# SparkFun_Ardumoto.net
KiCad netlist of a schematic drawn in EAGLE
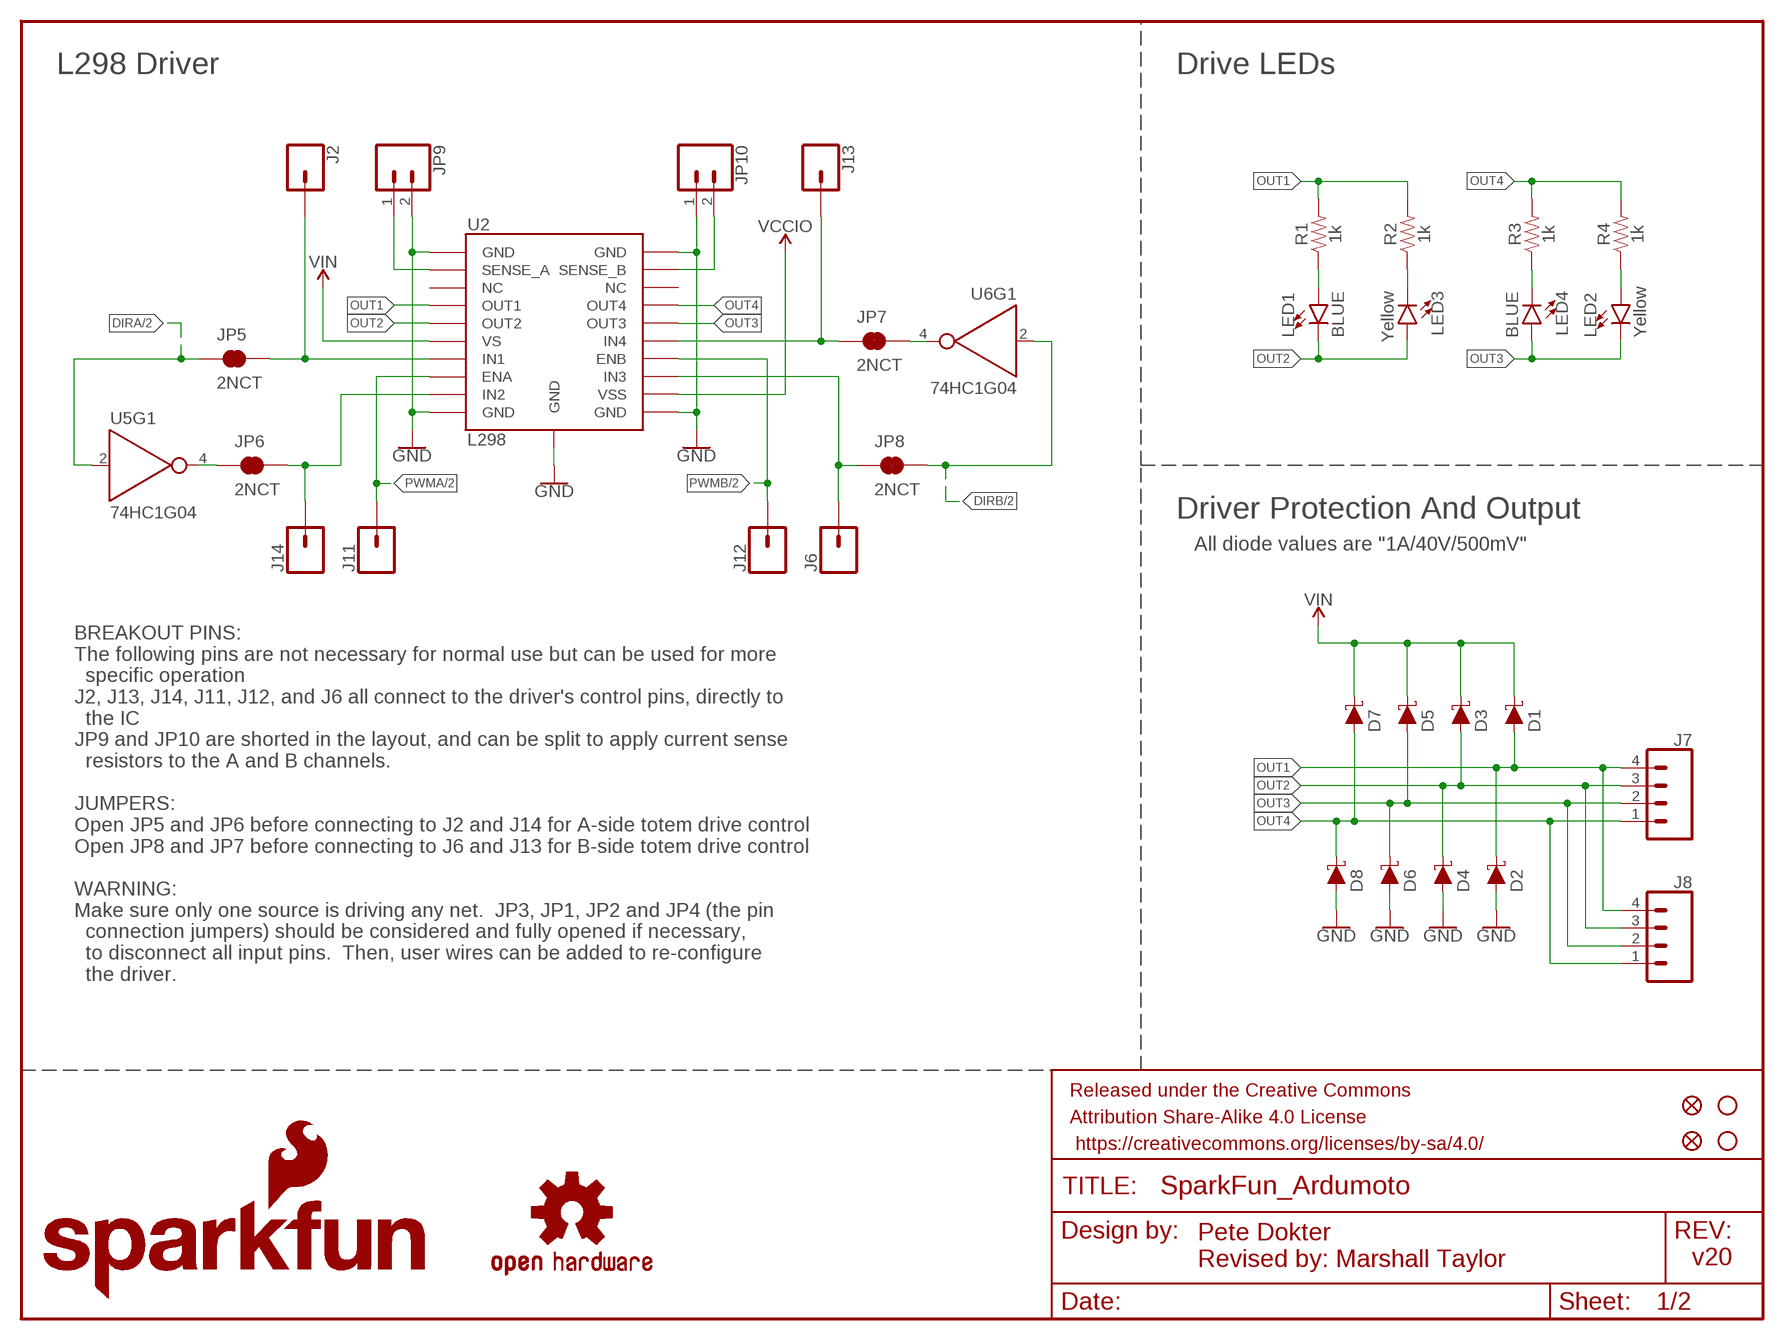
[diagram p0: schematic, sheet 1]
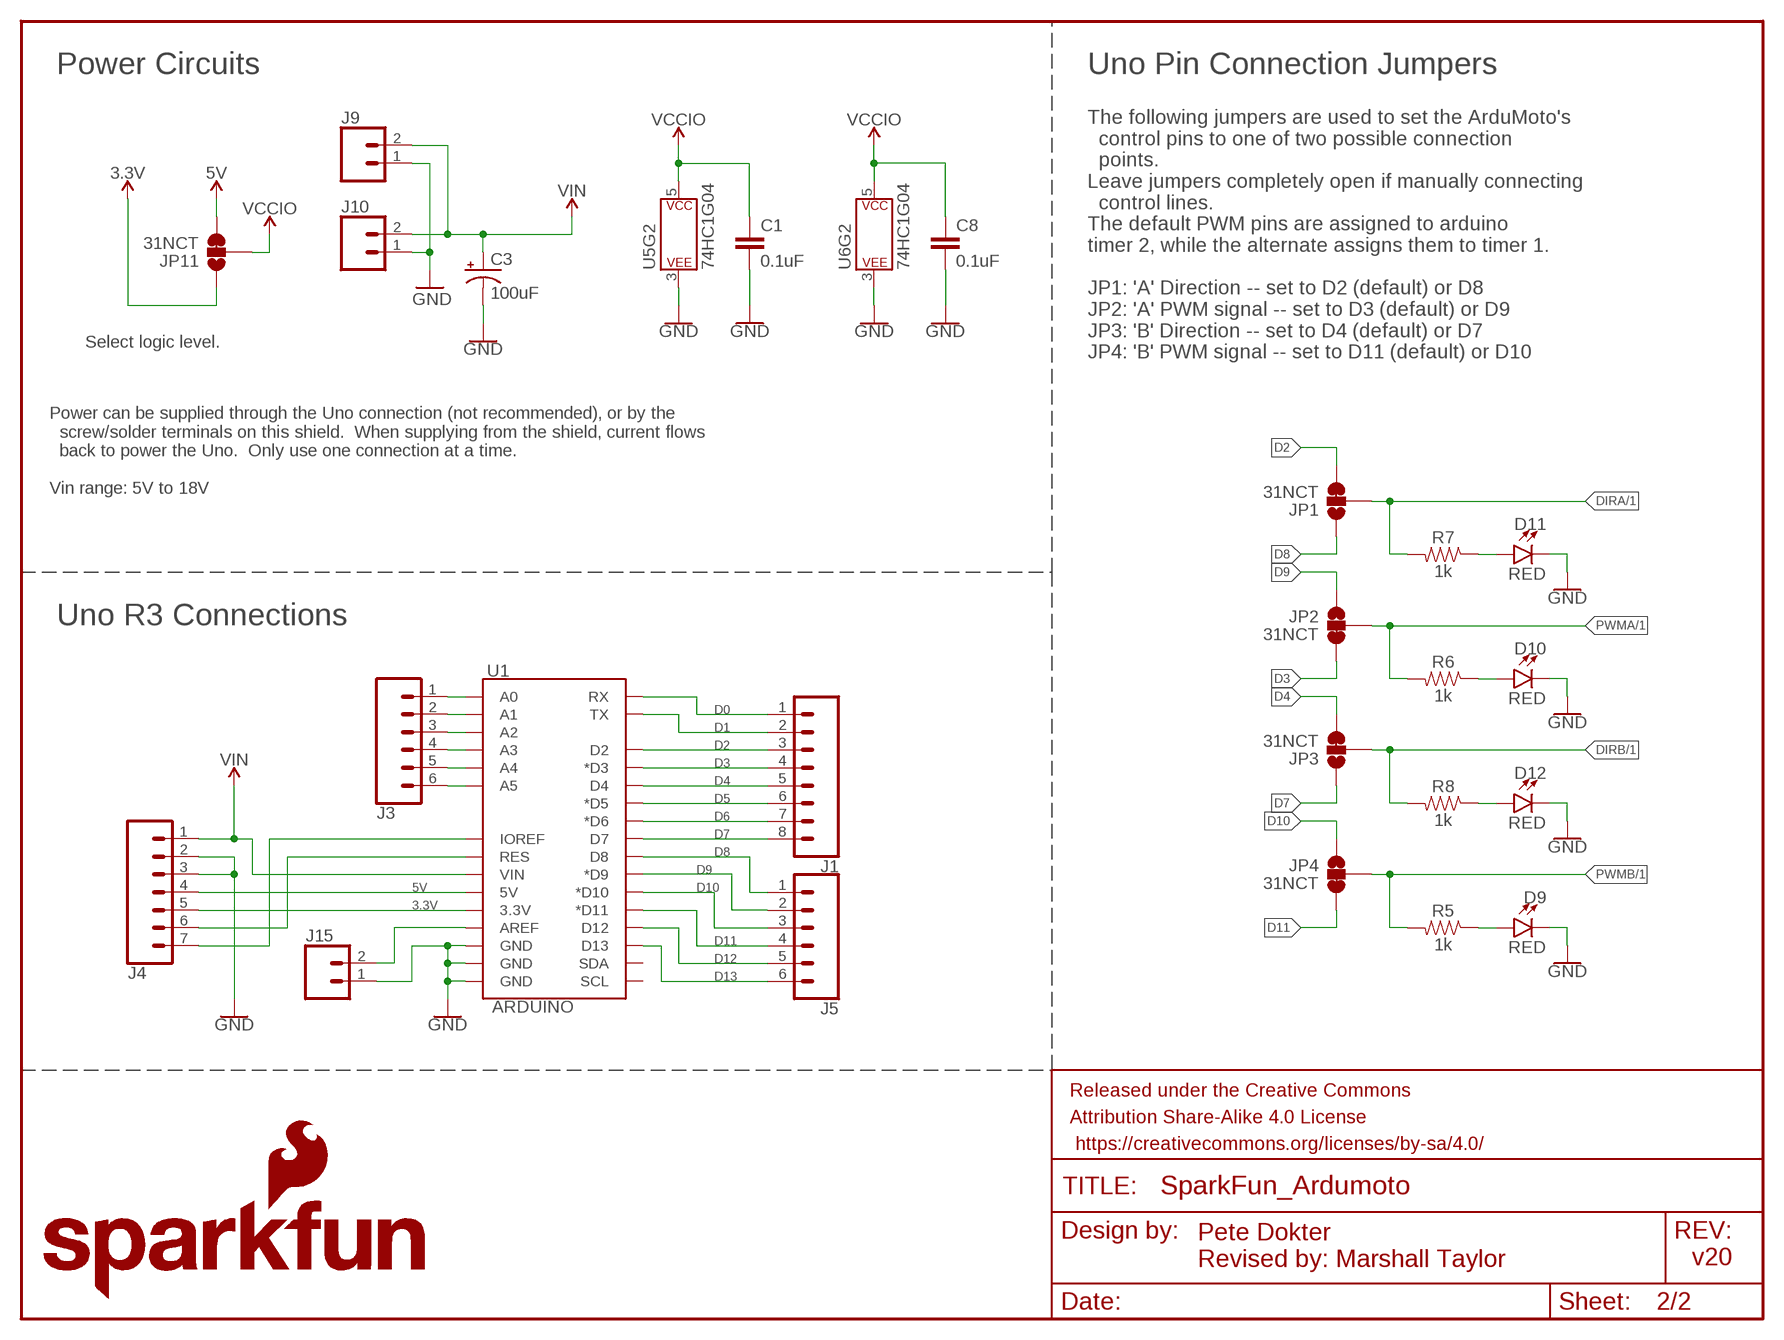
[diagram p1: schematic, sheet 2]

(export (version "E")
  (design (tool "Eeschema 10.0.6"))
  (components
    (comp (ref "D1")
      (value "1A/40V/500mV")
      (footprint "eagle-import:SMA-DIODE")
      (libsource (lib "eagle-import") (part "DIODE-SCHOTTKY-SS14"))
    )
    (comp (ref "D2")
      (value "1A/40V/500mV")
      (footprint "eagle-import:SMA-DIODE")
      (libsource (lib "eagle-import") (part "DIODE-SCHOTTKY-SS14"))
    )
    (comp (ref "D3")
      (value "1A/40V/500mV")
      (footprint "eagle-import:SMA-DIODE")
      (libsource (lib "eagle-import") (part "DIODE-SCHOTTKY-SS14"))
    )
    (comp (ref "D4")
      (value "1A/40V/500mV")
      (footprint "eagle-import:SMA-DIODE")
      (libsource (lib "eagle-import") (part "DIODE-SCHOTTKY-SS14"))
    )
    (comp (ref "D5")
      (value "1A/40V/500mV")
      (footprint "eagle-import:SMA-DIODE")
      (libsource (lib "eagle-import") (part "DIODE-SCHOTTKY-SS14"))
    )
    (comp (ref "D6")
      (value "1A/40V/500mV")
      (footprint "eagle-import:SMA-DIODE")
      (libsource (lib "eagle-import") (part "DIODE-SCHOTTKY-SS14"))
    )
    (comp (ref "D7")
      (value "1A/40V/500mV")
      (footprint "eagle-import:SMA-DIODE")
      (libsource (lib "eagle-import") (part "DIODE-SCHOTTKY-SS14"))
    )
    (comp (ref "D8")
      (value "1A/40V/500mV")
      (footprint "eagle-import:SMA-DIODE")
      (libsource (lib "eagle-import") (part "DIODE-SCHOTTKY-SS14"))
    )
    (comp (ref "FD1")
      (value "FIDUCIALUFIDUCIAL")
      (footprint "eagle-import:MICRO-FIDUCIAL")
      (libsource (lib "eagle-import") (part "FIDUCIALUFIDUCIAL"))
    )
    (comp (ref "FD2")
      (value "FIDUCIALUFIDUCIAL")
      (footprint "eagle-import:MICRO-FIDUCIAL")
      (libsource (lib "eagle-import") (part "FIDUCIALUFIDUCIAL"))
    )
    (comp (ref "FRAME2")
      (value "FRAME-LETTERNO_PACKAGE")
      (footprint "eagle-import:DUMMY")
      (fields (field (name "DESIGNER") "Nobody"))
      (libsource (lib "eagle-import") (part "FRAME-LETTERNO_PACKAGE"))
    )
    (comp (ref "H1")
      (value "STAND-OFF")
      (footprint "eagle-import:STAND-OFF")
      (libsource (lib "eagle-import") (part "STAND-OFF"))
    )
    (comp (ref "H2")
      (value "STAND-OFF")
      (footprint "eagle-import:STAND-OFF")
      (libsource (lib "eagle-import") (part "STAND-OFF"))
    )
    (comp (ref "J2")
      (value "CONN_01PTH_NO_SILK_YES_STOP")
      (footprint "eagle-import:1X01_NO_SILK")
      (libsource (lib "eagle-import") (part "CONN_01PTH_NO_SILK_YES_STOP"))
    )
    (comp (ref "J6")
      (value "CONN_01PTH_NO_SILK_YES_STOP")
      (footprint "eagle-import:1X01_NO_SILK")
      (libsource (lib "eagle-import") (part "CONN_01PTH_NO_SILK_YES_STOP"))
    )
    (comp (ref "J7")
      (value "CONN_04SCREW")
      (footprint "eagle-import:SCREWTERMINAL-3.5MM-4")
      (libsource (lib "eagle-import") (part "CONN_04SCREW"))
    )
    (comp (ref "J8")
      (value "CONN_04")
      (footprint "eagle-import:1X04")
      (libsource (lib "eagle-import") (part "CONN_04"))
    )
    (comp (ref "J11")
      (value "CONN_01PTH_NO_SILK_YES_STOP")
      (footprint "eagle-import:1X01_NO_SILK")
      (libsource (lib "eagle-import") (part "CONN_01PTH_NO_SILK_YES_STOP"))
    )
    (comp (ref "J12")
      (value "CONN_01PTH_NO_SILK_YES_STOP")
      (footprint "eagle-import:1X01_NO_SILK")
      (libsource (lib "eagle-import") (part "CONN_01PTH_NO_SILK_YES_STOP"))
    )
    (comp (ref "J13")
      (value "CONN_01PTH_NO_SILK_YES_STOP")
      (footprint "eagle-import:1X01_NO_SILK")
      (libsource (lib "eagle-import") (part "CONN_01PTH_NO_SILK_YES_STOP"))
    )
    (comp (ref "J14")
      (value "CONN_01PTH_NO_SILK_YES_STOP")
      (footprint "eagle-import:1X01_NO_SILK")
      (libsource (lib "eagle-import") (part "CONN_01PTH_NO_SILK_YES_STOP"))
    )
    (comp (ref "JP5")
      (value "2NCT")
      (footprint "eagle-import:SMT-JUMPER_2_NC_TRACE_SILK")
      (libsource (lib "eagle-import") (part "JUMPER-SMT_2_NC_TRACE_SILK"))
    )
    (comp (ref "JP6")
      (value "2NCT")
      (footprint "eagle-import:SMT-JUMPER_2_NC_TRACE_SILK")
      (libsource (lib "eagle-import") (part "JUMPER-SMT_2_NC_TRACE_SILK"))
    )
    (comp (ref "JP7")
      (value "2NCT")
      (footprint "eagle-import:SMT-JUMPER_2_NC_TRACE_SILK")
      (libsource (lib "eagle-import") (part "JUMPER-SMT_2_NC_TRACE_SILK"))
    )
    (comp (ref "JP8")
      (value "2NCT")
      (footprint "eagle-import:SMT-JUMPER_2_NC_TRACE_SILK")
      (libsource (lib "eagle-import") (part "JUMPER-SMT_2_NC_TRACE_SILK"))
    )
    (comp (ref "JP9")
      (value "CONN_021X02_NO_SILK")
      (footprint "eagle-import:1X02_NO_SILK")
      (libsource (lib "eagle-import") (part "CONN_021X02_NO_SILK"))
    )
    (comp (ref "JP10")
      (value "CONN_021X02_NO_SILK")
      (footprint "eagle-import:1X02_NO_SILK")
      (libsource (lib "eagle-import") (part "CONN_021X02_NO_SILK"))
    )
    (comp (ref "LED1")
      (value "BLUE")
      (footprint "eagle-import:LED-0603")
      (libsource (lib "eagle-import") (part "LED-BLUE0603"))
    )
    (comp (ref "LED2")
      (value "Yellow")
      (footprint "eagle-import:LED-0603")
      (libsource (lib "eagle-import") (part "LED-YELLOW0603"))
    )
    (comp (ref "LED3")
      (value "Yellow")
      (footprint "eagle-import:LED-0603")
      (libsource (lib "eagle-import") (part "LED-YELLOW0603"))
    )
    (comp (ref "LED4")
      (value "BLUE")
      (footprint "eagle-import:LED-0603")
      (libsource (lib "eagle-import") (part "LED-BLUE0603"))
    )
    (comp (ref "LOGO2")
      (value "SFE_LOGO_NAME_FLAME.1_INCH")
      (footprint "eagle-import:SFE_LOGO_NAME_FLAME_.1")
      (libsource (lib "eagle-import") (part "SFE_LOGO_NAME_FLAME.1_INCH"))
    )
    (comp (ref "R1")
      (value "1k")
      (footprint "eagle-import:0603")
      (libsource (lib "eagle-import") (part "1KOHM-0603-1/10W-1%"))
    )
    (comp (ref "R2")
      (value "1k")
      (footprint "eagle-import:0603")
      (libsource (lib "eagle-import") (part "1KOHM-0603-1/10W-1%"))
    )
    (comp (ref "R3")
      (value "1k")
      (footprint "eagle-import:0603")
      (libsource (lib "eagle-import") (part "1KOHM-0603-1/10W-1%"))
    )
    (comp (ref "R4")
      (value "1k")
      (footprint "eagle-import:0603")
      (libsource (lib "eagle-import") (part "1KOHM-0603-1/10W-1%"))
    )
    (comp (ref "U$1")
      (value "OSHW-LOGOS")
      (footprint "eagle-import:OSHW-LOGO-S")
      (libsource (lib "eagle-import") (part "OSHW-LOGOS"))
    )
    (comp (ref "U2")
      (value "L298")
      (footprint "eagle-import:POWERSO20_L298_PAD")
      (libsource (lib "eagle-import") (part "L298_SMD_W_PAD"))
    )
    (comp (ref "U5")
      (value "74HC1G04")
      (footprint "eagle-import:SOT353")
      (libsource (lib "eagle-import") (part "741G04HC"))
    )
    (comp (ref "U6")
      (value "74HC1G04")
      (footprint "eagle-import:SOT353")
      (libsource (lib "eagle-import") (part "741G04HC"))
    )
    (comp (ref "C1")
      (value "0.1uF")
      (footprint "eagle-import:0603")
      (libsource (lib "eagle-import") (part "0.1UF-0603-25V-5%"))
    )
    (comp (ref "C3")
      (value "100uF")
      (footprint "eagle-import:PANASONIC_D")
      (libsource (lib "eagle-import") (part "100UF-POLAR-25V-20%(ELEC)"))
    )
    (comp (ref "C8")
      (value "0.1uF")
      (footprint "eagle-import:0603")
      (libsource (lib "eagle-import") (part "0.1UF-0603-25V-5%"))
    )
    (comp (ref "D9")
      (value "RED")
      (footprint "eagle-import:LED-0603")
      (libsource (lib "eagle-import") (part "LED-RED0603"))
    )
    (comp (ref "D10")
      (value "RED")
      (footprint "eagle-import:LED-0603")
      (libsource (lib "eagle-import") (part "LED-RED0603"))
    )
    (comp (ref "D11")
      (value "RED")
      (footprint "eagle-import:LED-0603")
      (libsource (lib "eagle-import") (part "LED-RED0603"))
    )
    (comp (ref "D12")
      (value "RED")
      (footprint "eagle-import:LED-0603")
      (libsource (lib "eagle-import") (part "LED-RED0603"))
    )
    (comp (ref "FRAME1")
      (value "FRAME-LETTER")
      (footprint "eagle-import:CREATIVE_COMMONS")
      (libsource (lib "eagle-import") (part "FRAME-LETTER"))
    )
    (comp (ref "J1")
      (value "CONN_08NO_SILK_FEMALE_PTH")
      (footprint "eagle-import:1X08_NO_SILK")
      (libsource (lib "eagle-import") (part "CONN_08NO_SILK_FEMALE_PTH"))
    )
    (comp (ref "J3")
      (value "CONN_06NO_SILK_FEMALE_PTH")
      (footprint "eagle-import:1X06_NO_SILK")
      (libsource (lib "eagle-import") (part "CONN_06NO_SILK_FEMALE_PTH"))
    )
    (comp (ref "J4")
      (value "CONN_07NO_SILK")
      (footprint "eagle-import:1X07_NO_SILK")
      (libsource (lib "eagle-import") (part "CONN_07NO_SILK"))
    )
    (comp (ref "J5")
      (value "CONN_06NO_SILK_FEMALE_PTH")
      (footprint "eagle-import:1X06_NO_SILK")
      (libsource (lib "eagle-import") (part "CONN_06NO_SILK_FEMALE_PTH"))
    )
    (comp (ref "J9")
      (value "CONN_02")
      (footprint "eagle-import:1X02")
      (libsource (lib "eagle-import") (part "CONN_02"))
    )
    (comp (ref "J10")
      (value "CONN_023.5MM")
      (footprint "eagle-import:SCREWTERMINAL-3.5MM-2")
      (libsource (lib "eagle-import") (part "CONN_023.5MM"))
    )
    (comp (ref "J15")
      (value "CONN_021X02_NO_SILK")
      (footprint "eagle-import:1X02_NO_SILK")
      (libsource (lib "eagle-import") (part "CONN_021X02_NO_SILK"))
    )
    (comp (ref "JP1")
      (value "31NCT")
      (footprint "eagle-import:SMT-JUMPER_3_1-NC_TRACE_SILK")
      (libsource (lib "eagle-import") (part "JUMPER-SMT_3_1-NC_TRACE_SILK"))
    )
    (comp (ref "JP2")
      (value "31NCT")
      (footprint "eagle-import:SMT-JUMPER_3_1-NC_TRACE_SILK")
      (libsource (lib "eagle-import") (part "JUMPER-SMT_3_1-NC_TRACE_SILK"))
    )
    (comp (ref "JP3")
      (value "31NCT")
      (footprint "eagle-import:SMT-JUMPER_3_1-NC_TRACE_SILK")
      (libsource (lib "eagle-import") (part "JUMPER-SMT_3_1-NC_TRACE_SILK"))
    )
    (comp (ref "JP4")
      (value "31NCT")
      (footprint "eagle-import:SMT-JUMPER_3_1-NC_TRACE_SILK")
      (libsource (lib "eagle-import") (part "JUMPER-SMT_3_1-NC_TRACE_SILK"))
    )
    (comp (ref "JP11")
      (value "31NCT")
      (footprint "eagle-import:SMT-JUMPER_3_1-NC_TRACE_SILK")
      (libsource (lib "eagle-import") (part "JUMPER-SMT_3_1-NC_TRACE_SILK"))
    )
    (comp (ref "LOGO1")
      (value "SFE_LOGO_NAME_FLAME.2_INCH")
      (footprint "eagle-import:SFE_LOGO_NAME_FLAME_.2")
      (libsource (lib "eagle-import") (part "SFE_LOGO_NAME_FLAME.2_INCH"))
    )
    (comp (ref "R5")
      (value "1k")
      (footprint "eagle-import:0603")
      (libsource (lib "eagle-import") (part "1KOHM-0603-1/10W-1%"))
    )
    (comp (ref "R6")
      (value "1k")
      (footprint "eagle-import:0603")
      (libsource (lib "eagle-import") (part "1KOHM-0603-1/10W-1%"))
    )
    (comp (ref "R7")
      (value "1k")
      (footprint "eagle-import:0603")
      (libsource (lib "eagle-import") (part "1KOHM-0603-1/10W-1%"))
    )
    (comp (ref "R8")
      (value "1k")
      (footprint "eagle-import:0603")
      (libsource (lib "eagle-import") (part "1KOHM-0603-1/10W-1%"))
    )
    (comp (ref "U1")
      (value "ARDUINO")
      (footprint "eagle-import:UNO_R3_SHIELD_NOLABELS")
      (libsource (lib "eagle-import") (part "ARDUINO_UNO_R3_SHIELDNOLABELS"))
    )
  )
  (nets
    (net (code "1") (name "3.3V") (class "Default")
      (node (ref "J4") (pin "5") (pinfunction "5_5") (pintype "passive"))
      (node (ref "JP11") (pin "1") (pinfunction "1_1") (pintype "passive"))
      (node (ref "U1") (pin "3.3V") (pinfunction "3.3V_3.3V") (pintype "bidirectional"))
    )
    (net (code "2") (name "5V") (class "Default")
      (node (ref "J4") (pin "4") (pinfunction "4_4") (pintype "passive"))
      (node (ref "JP11") (pin "3") (pinfunction "3_3") (pintype "passive"))
      (node (ref "U1") (pin "5V") (pinfunction "5V_5V") (pintype "bidirectional"))
    )
    (net (code "3") (name "D0") (class "Default")
      (node (ref "J1") (pin "1") (pinfunction "1_1") (pintype "passive"))
      (node (ref "U1") (pin "RX") (pinfunction "RX_RX") (pintype "bidirectional"))
    )
    (net (code "4") (name "D1") (class "Default")
      (node (ref "J1") (pin "2") (pinfunction "2_2") (pintype "passive"))
      (node (ref "U1") (pin "TX") (pinfunction "TX_TX") (pintype "bidirectional"))
    )
    (net (code "5") (name "D2") (class "Default")
      (node (ref "J1") (pin "3") (pinfunction "3_3") (pintype "passive"))
      (node (ref "JP1") (pin "3") (pinfunction "3_3") (pintype "passive"))
      (node (ref "U1") (pin "D2") (pinfunction "D2_D2") (pintype "bidirectional"))
    )
    (net (code "6") (name "D3") (class "Default")
      (node (ref "J1") (pin "4") (pinfunction "4_4") (pintype "passive"))
      (node (ref "JP2") (pin "3") (pinfunction "3_3") (pintype "passive"))
      (node (ref "U1") (pin "D3") (pinfunction "*D3_D3") (pintype "bidirectional"))
    )
    (net (code "7") (name "D4") (class "Default")
      (node (ref "J1") (pin "5") (pinfunction "5_5") (pintype "passive"))
      (node (ref "JP3") (pin "3") (pinfunction "3_3") (pintype "passive"))
      (node (ref "U1") (pin "D4") (pinfunction "D4_D4") (pintype "bidirectional"))
    )
    (net (code "8") (name "D5") (class "Default")
      (node (ref "J1") (pin "6") (pinfunction "6_6") (pintype "passive"))
      (node (ref "U1") (pin "D5") (pinfunction "*D5_D5") (pintype "bidirectional"))
    )
    (net (code "9") (name "D6") (class "Default")
      (node (ref "J1") (pin "7") (pinfunction "7_7") (pintype "passive"))
      (node (ref "U1") (pin "D6") (pinfunction "*D6_D6") (pintype "bidirectional"))
    )
    (net (code "10") (name "D7") (class "Default")
      (node (ref "J1") (pin "8") (pinfunction "8_8") (pintype "passive"))
      (node (ref "JP3") (pin "1") (pinfunction "1_1") (pintype "passive"))
      (node (ref "U1") (pin "D7") (pinfunction "D7_D7") (pintype "bidirectional"))
    )
    (net (code "11") (name "D8") (class "Default")
      (node (ref "J5") (pin "1") (pinfunction "1_1") (pintype "passive"))
      (node (ref "JP1") (pin "1") (pinfunction "1_1") (pintype "passive"))
      (node (ref "U1") (pin "D8") (pinfunction "D8_D8") (pintype "bidirectional"))
    )
    (net (code "12") (name "D9") (class "Default")
      (node (ref "J5") (pin "2") (pinfunction "2_2") (pintype "passive"))
      (node (ref "JP2") (pin "1") (pinfunction "1_1") (pintype "passive"))
      (node (ref "U1") (pin "D9") (pinfunction "*D9_D9") (pintype "bidirectional"))
    )
    (net (code "13") (name "D10") (class "Default")
      (node (ref "J5") (pin "3") (pinfunction "3_3") (pintype "passive"))
      (node (ref "JP4") (pin "1") (pinfunction "1_1") (pintype "passive"))
      (node (ref "U1") (pin "D10") (pinfunction "*D10_D10") (pintype "bidirectional"))
    )
    (net (code "14") (name "D11") (class "Default")
      (node (ref "J5") (pin "4") (pinfunction "4_4") (pintype "passive"))
      (node (ref "JP4") (pin "3") (pinfunction "3_3") (pintype "passive"))
      (node (ref "U1") (pin "D11") (pinfunction "*D11_D11") (pintype "bidirectional"))
    )
    (net (code "15") (name "D12") (class "Default")
      (node (ref "J5") (pin "5") (pinfunction "5_5") (pintype "passive"))
      (node (ref "U1") (pin "D12") (pinfunction "D12_D12") (pintype "bidirectional"))
    )
    (net (code "16") (name "D13") (class "Default")
      (node (ref "J5") (pin "6") (pinfunction "6_6") (pintype "passive"))
      (node (ref "U1") (pin "D13") (pinfunction "D13_D13") (pintype "bidirectional"))
    )
    (net (code "17") (name "DIRA") (class "Default")
      (node (ref "JP1") (pin "2") (pinfunction "2_2") (pintype "passive"))
      (node (ref "JP5") (pin "1") (pinfunction "1_1") (pintype "passive"))
      (node (ref "R7") (pin "2") (pinfunction "2_2") (pintype "passive"))
      (node (ref "U5") (pin "2") (pinfunction "A_2") (pintype "bidirectional"))
    )
    (net (code "18") (name "DIRB") (class "Default")
      (node (ref "JP3") (pin "2") (pinfunction "2_2") (pintype "passive"))
      (node (ref "JP8") (pin "2") (pinfunction "2_2") (pintype "passive"))
      (node (ref "R8") (pin "2") (pinfunction "2_2") (pintype "passive"))
      (node (ref "U6") (pin "2") (pinfunction "A_2") (pintype "bidirectional"))
    )
    (net (code "19") (name "GND") (class "Default")
      (node (ref "C1") (pin "2") (pinfunction "2_2") (pintype "passive"))
      (node (ref "C3") (pin "-") (pinfunction "-_-") (pintype "passive"))
      (node (ref "C8") (pin "2") (pinfunction "2_2") (pintype "passive"))
      (node (ref "D10") (pin "C") (pinfunction "C_C") (pintype "passive"))
      (node (ref "D11") (pin "C") (pinfunction "C_C") (pintype "passive"))
      (node (ref "D12") (pin "C") (pinfunction "C_C") (pintype "passive"))
      (node (ref "D2") (pin "A") (pinfunction "A_A") (pintype "passive"))
      (node (ref "D4") (pin "A") (pinfunction "A_A") (pintype "passive"))
      (node (ref "D6") (pin "A") (pinfunction "A_A") (pintype "passive"))
      (node (ref "D8") (pin "A") (pinfunction "A_A") (pintype "passive"))
      (node (ref "D9") (pin "C") (pinfunction "C_C") (pintype "passive"))
      (node (ref "J10") (pin "1") (pinfunction "1_1") (pintype "passive"))
      (node (ref "J15") (pin "1") (pinfunction "1_1") (pintype "passive"))
      (node (ref "J4") (pin "2") (pinfunction "2_2") (pintype "passive"))
      (node (ref "J4") (pin "3") (pinfunction "3_3") (pintype "passive"))
      (node (ref "J9") (pin "1") (pinfunction "1_1") (pintype "passive"))
      (node (ref "JP10") (pin "1") (pinfunction "1_1") (pintype "passive"))
      (node (ref "JP9") (pin "2") (pinfunction "2_2") (pintype "passive"))
      (node (ref "U1") (pin "GND@0") (pinfunction "GND_GND@0") (pintype "bidirectional"))
      (node (ref "U1") (pin "GND@1") (pinfunction "GND_GND@1") (pintype "bidirectional"))
      (node (ref "U1") (pin "GND@2") (pinfunction "GND_GND@2") (pintype "bidirectional"))
      (node (ref "U2") (pin "1") (pinfunction "GND_1") (pintype "bidirectional"))
      (node (ref "U2") (pin "10") (pinfunction "GND_10") (pintype "bidirectional"))
      (node (ref "U2") (pin "11") (pinfunction "GND_11") (pintype "bidirectional"))
      (node (ref "U2") (pin "20") (pinfunction "GND_20") (pintype "bidirectional"))
      (node (ref "U2") (pin "PAD") (pinfunction "GND_PAD") (pintype "bidirectional"))
      (node (ref "U5") (pin "3") (pinfunction "P$V-_3") (pintype "bidirectional"))
      (node (ref "U6") (pin "3") (pinfunction "P$V-_3") (pintype "bidirectional"))
    )
    (net (code "20") (name "Net-(D9-PadA)") (class "Default")
      (node (ref "D9") (pin "A") (pinfunction "A_A") (pintype "passive"))
      (node (ref "R5") (pin "1") (pinfunction "1_1") (pintype "passive"))
    )
    (net (code "21") (name "Net-(D10-PadA)") (class "Default")
      (node (ref "D10") (pin "A") (pinfunction "A_A") (pintype "passive"))
      (node (ref "R6") (pin "1") (pinfunction "1_1") (pintype "passive"))
    )
    (net (code "22") (name "Net-(D11-PadA)") (class "Default")
      (node (ref "D11") (pin "A") (pinfunction "A_A") (pintype "passive"))
      (node (ref "R7") (pin "1") (pinfunction "1_1") (pintype "passive"))
    )
    (net (code "23") (name "Net-(D12-PadA)") (class "Default")
      (node (ref "D12") (pin "A") (pinfunction "A_A") (pintype "passive"))
      (node (ref "R8") (pin "1") (pinfunction "1_1") (pintype "passive"))
    )
    (net (code "24") (name "Net-(J3-Pad1)") (class "Default")
      (node (ref "J3") (pin "1") (pinfunction "1_1") (pintype "passive"))
      (node (ref "U1") (pin "A0") (pinfunction "A0_A0") (pintype "bidirectional"))
    )
    (net (code "25") (name "Net-(J3-Pad2)") (class "Default")
      (node (ref "J3") (pin "2") (pinfunction "2_2") (pintype "passive"))
      (node (ref "U1") (pin "A1") (pinfunction "A1_A1") (pintype "bidirectional"))
    )
    (net (code "26") (name "Net-(J3-Pad3)") (class "Default")
      (node (ref "J3") (pin "3") (pinfunction "3_3") (pintype "passive"))
      (node (ref "U1") (pin "A2") (pinfunction "A2_A2") (pintype "bidirectional"))
    )
    (net (code "27") (name "Net-(J3-Pad4)") (class "Default")
      (node (ref "J3") (pin "4") (pinfunction "4_4") (pintype "passive"))
      (node (ref "U1") (pin "A3") (pinfunction "A3_A3") (pintype "bidirectional"))
    )
    (net (code "28") (name "Net-(J3-Pad5)") (class "Default")
      (node (ref "J3") (pin "5") (pinfunction "5_5") (pintype "passive"))
      (node (ref "U1") (pin "A4") (pinfunction "A4_A4") (pintype "bidirectional"))
    )
    (net (code "29") (name "Net-(J3-Pad6)") (class "Default")
      (node (ref "J3") (pin "6") (pinfunction "6_6") (pintype "passive"))
      (node (ref "U1") (pin "A5") (pinfunction "A5_A5") (pintype "bidirectional"))
    )
    (net (code "30") (name "Net-(J4-Pad6)") (class "Default")
      (node (ref "J4") (pin "6") (pinfunction "6_6") (pintype "passive"))
      (node (ref "U1") (pin "RES") (pinfunction "RES_RES") (pintype "bidirectional"))
    )
    (net (code "31") (name "Net-(J4-Pad7)") (class "Default")
      (node (ref "J4") (pin "7") (pinfunction "7_7") (pintype "passive"))
      (node (ref "U1") (pin "IOREF") (pinfunction "IOREF_IOREF") (pintype "bidirectional"))
    )
    (net (code "32") (name "Net-(J15-Pad2)") (class "Default")
      (node (ref "J15") (pin "2") (pinfunction "2_2") (pintype "passive"))
      (node (ref "U1") (pin "AREF") (pinfunction "AREF_AREF") (pintype "bidirectional"))
    )
    (net (code "33") (name "Net-(LED1-PadA)") (class "Default")
      (node (ref "LED1") (pin "A") (pinfunction "A_A") (pintype "passive"))
      (node (ref "R1") (pin "1") (pinfunction "1_1") (pintype "passive"))
    )
    (net (code "34") (name "Net-(LED2-PadA)") (class "Default")
      (node (ref "LED2") (pin "A") (pinfunction "A_A") (pintype "passive"))
      (node (ref "R4") (pin "1") (pinfunction "1_1") (pintype "passive"))
    )
    (net (code "35") (name "Net-(LED3-PadC)") (class "Default")
      (node (ref "LED3") (pin "C") (pinfunction "C_C") (pintype "passive"))
      (node (ref "R2") (pin "1") (pinfunction "1_1") (pintype "passive"))
    )
    (net (code "36") (name "Net-(LED4-PadC)") (class "Default")
      (node (ref "LED4") (pin "C") (pinfunction "C_C") (pintype "passive"))
      (node (ref "R3") (pin "1") (pinfunction "1_1") (pintype "passive"))
    )
    (net (code "37") (name "Net-(U2-IN1)") (class "Default")
      (node (ref "J2") (pin "1") (pinfunction "1_1") (pintype "passive"))
      (node (ref "JP5") (pin "2") (pinfunction "2_2") (pintype "passive"))
      (node (ref "U2") (pin "7") (pinfunction "IN1_7") (pintype "bidirectional"))
    )
    (net (code "38") (name "Net-(U2-IN2)") (class "Default")
      (node (ref "J14") (pin "1") (pinfunction "1_1") (pintype "passive"))
      (node (ref "JP6") (pin "2") (pinfunction "2_2") (pintype "passive"))
      (node (ref "U2") (pin "9") (pinfunction "IN2_9") (pintype "bidirectional"))
    )
    (net (code "39") (name "Net-(U2-IN3)") (class "Default")
      (node (ref "J6") (pin "1") (pinfunction "1_1") (pintype "passive"))
      (node (ref "JP8") (pin "1") (pinfunction "1_1") (pintype "passive"))
      (node (ref "U2") (pin "13") (pinfunction "IN3_13") (pintype "bidirectional"))
    )
    (net (code "40") (name "Net-(U2-IN4)") (class "Default")
      (node (ref "J13") (pin "1") (pinfunction "1_1") (pintype "passive"))
      (node (ref "JP7") (pin "1") (pinfunction "1_1") (pintype "passive"))
      (node (ref "U2") (pin "15") (pinfunction "IN4_15") (pintype "bidirectional"))
    )
    (net (code "41") (name "Net-(U2-SENSE_A)") (class "Default")
      (node (ref "JP9") (pin "1") (pinfunction "1_1") (pintype "passive"))
      (node (ref "U2") (pin "2") (pinfunction "SENSE_A_2") (pintype "bidirectional"))
    )
    (net (code "42") (name "Net-(U2-SENSE_B)") (class "Default")
      (node (ref "JP10") (pin "2") (pinfunction "2_2") (pintype "passive"))
      (node (ref "U2") (pin "19") (pinfunction "SENSE_B_19") (pintype "bidirectional"))
    )
    (net (code "43") (name "Net-(U5A-Y)") (class "Default")
      (node (ref "JP6") (pin "1") (pinfunction "1_1") (pintype "passive"))
      (node (ref "U5") (pin "4") (pinfunction "Y_4") (pintype "bidirectional"))
    )
    (net (code "44") (name "Net-(U6A-Y)") (class "Default")
      (node (ref "JP7") (pin "2") (pinfunction "2_2") (pintype "passive"))
      (node (ref "U6") (pin "4") (pinfunction "Y_4") (pintype "bidirectional"))
    )
    (net (code "45") (name "OUT1") (class "Default")
      (node (ref "D1") (pin "A") (pinfunction "A_A") (pintype "passive"))
      (node (ref "D2") (pin "C") (pinfunction "C_C") (pintype "passive"))
      (node (ref "J7") (pin "4") (pinfunction "4_4") (pintype "passive"))
      (node (ref "J8") (pin "4") (pinfunction "4_4") (pintype "passive"))
      (node (ref "R1") (pin "2") (pinfunction "2_2") (pintype "passive"))
      (node (ref "R2") (pin "2") (pinfunction "2_2") (pintype "passive"))
      (node (ref "U2") (pin "4") (pinfunction "OUT1_4") (pintype "bidirectional"))
    )
    (net (code "46") (name "OUT2") (class "Default")
      (node (ref "D3") (pin "A") (pinfunction "A_A") (pintype "passive"))
      (node (ref "D4") (pin "C") (pinfunction "C_C") (pintype "passive"))
      (node (ref "J7") (pin "3") (pinfunction "3_3") (pintype "passive"))
      (node (ref "J8") (pin "3") (pinfunction "3_3") (pintype "passive"))
      (node (ref "LED1") (pin "C") (pinfunction "C_C") (pintype "passive"))
      (node (ref "LED3") (pin "A") (pinfunction "A_A") (pintype "passive"))
      (node (ref "U2") (pin "5") (pinfunction "OUT2_5") (pintype "bidirectional"))
    )
    (net (code "47") (name "OUT3") (class "Default")
      (node (ref "D5") (pin "A") (pinfunction "A_A") (pintype "passive"))
      (node (ref "D6") (pin "C") (pinfunction "C_C") (pintype "passive"))
      (node (ref "J7") (pin "2") (pinfunction "2_2") (pintype "passive"))
      (node (ref "J8") (pin "2") (pinfunction "2_2") (pintype "passive"))
      (node (ref "LED2") (pin "C") (pinfunction "C_C") (pintype "passive"))
      (node (ref "LED4") (pin "A") (pinfunction "A_A") (pintype "passive"))
      (node (ref "U2") (pin "16") (pinfunction "OUT3_16") (pintype "bidirectional"))
    )
    (net (code "48") (name "OUT4") (class "Default")
      (node (ref "D7") (pin "A") (pinfunction "A_A") (pintype "passive"))
      (node (ref "D8") (pin "C") (pinfunction "C_C") (pintype "passive"))
      (node (ref "J7") (pin "1") (pinfunction "1_1") (pintype "passive"))
      (node (ref "J8") (pin "1") (pinfunction "1_1") (pintype "passive"))
      (node (ref "R3") (pin "2") (pinfunction "2_2") (pintype "passive"))
      (node (ref "R4") (pin "2") (pinfunction "2_2") (pintype "passive"))
      (node (ref "U2") (pin "17") (pinfunction "OUT4_17") (pintype "bidirectional"))
    )
    (net (code "49") (name "PWMA") (class "Default")
      (node (ref "J11") (pin "1") (pinfunction "1_1") (pintype "passive"))
      (node (ref "JP2") (pin "2") (pinfunction "2_2") (pintype "passive"))
      (node (ref "R6") (pin "2") (pinfunction "2_2") (pintype "passive"))
      (node (ref "U2") (pin "8") (pinfunction "ENA_8") (pintype "bidirectional"))
    )
    (net (code "50") (name "PWMB") (class "Default")
      (node (ref "J12") (pin "1") (pinfunction "1_1") (pintype "passive"))
      (node (ref "JP4") (pin "2") (pinfunction "2_2") (pintype "passive"))
      (node (ref "R5") (pin "2") (pinfunction "2_2") (pintype "passive"))
      (node (ref "U2") (pin "14") (pinfunction "ENB_14") (pintype "bidirectional"))
    )
    (net (code "51") (name "VCCIO") (class "Default")
      (node (ref "C1") (pin "1") (pinfunction "1_1") (pintype "passive"))
      (node (ref "C8") (pin "1") (pinfunction "1_1") (pintype "passive"))
      (node (ref "JP11") (pin "2") (pinfunction "2_2") (pintype "passive"))
      (node (ref "U2") (pin "12") (pinfunction "VSS_12") (pintype "bidirectional"))
      (node (ref "U5") (pin "5") (pinfunction "P$V+_5") (pintype "bidirectional"))
      (node (ref "U6") (pin "5") (pinfunction "P$V+_5") (pintype "bidirectional"))
    )
    (net (code "52") (name "VIN") (class "Default")
      (node (ref "C3") (pin "+") (pinfunction "+_+") (pintype "passive"))
      (node (ref "D1") (pin "C") (pinfunction "C_C") (pintype "passive"))
      (node (ref "D3") (pin "C") (pinfunction "C_C") (pintype "passive"))
      (node (ref "D5") (pin "C") (pinfunction "C_C") (pintype "passive"))
      (node (ref "D7") (pin "C") (pinfunction "C_C") (pintype "passive"))
      (node (ref "J10") (pin "2") (pinfunction "2_2") (pintype "passive"))
      (node (ref "J4") (pin "1") (pinfunction "1_1") (pintype "passive"))
      (node (ref "J9") (pin "2") (pinfunction "2_2") (pintype "passive"))
      (node (ref "U1") (pin "VIN") (pinfunction "VIN_VIN") (pintype "bidirectional"))
      (node (ref "U2") (pin "6") (pinfunction "VS_6") (pintype "bidirectional"))
    )
    (net (code "53") (name "unconnected-(U1-PadSCL)") (class "Default")
      (node (ref "U1") (pin "SCL") (pinfunction "SCL_SCL") (pintype "bidirectional"))
    )
    (net (code "54") (name "unconnected-(U1-PadSDA)") (class "Default")
      (node (ref "U1") (pin "SDA") (pinfunction "SDA_SDA") (pintype "bidirectional"))
    )
    (net (code "55") (name "unconnected-(U2-NC-Pad3)") (class "Default")
      (node (ref "U2") (pin "3") (pinfunction "NC_3") (pintype "bidirectional"))
    )
    (net (code "56") (name "unconnected-(U2-NC-Pad18)") (class "Default")
      (node (ref "U2") (pin "18") (pinfunction "NC_18") (pintype "bidirectional"))
    )
  )
)
